# Test_Board.net
KiCad netlist of a schematic drawn in EAGLE
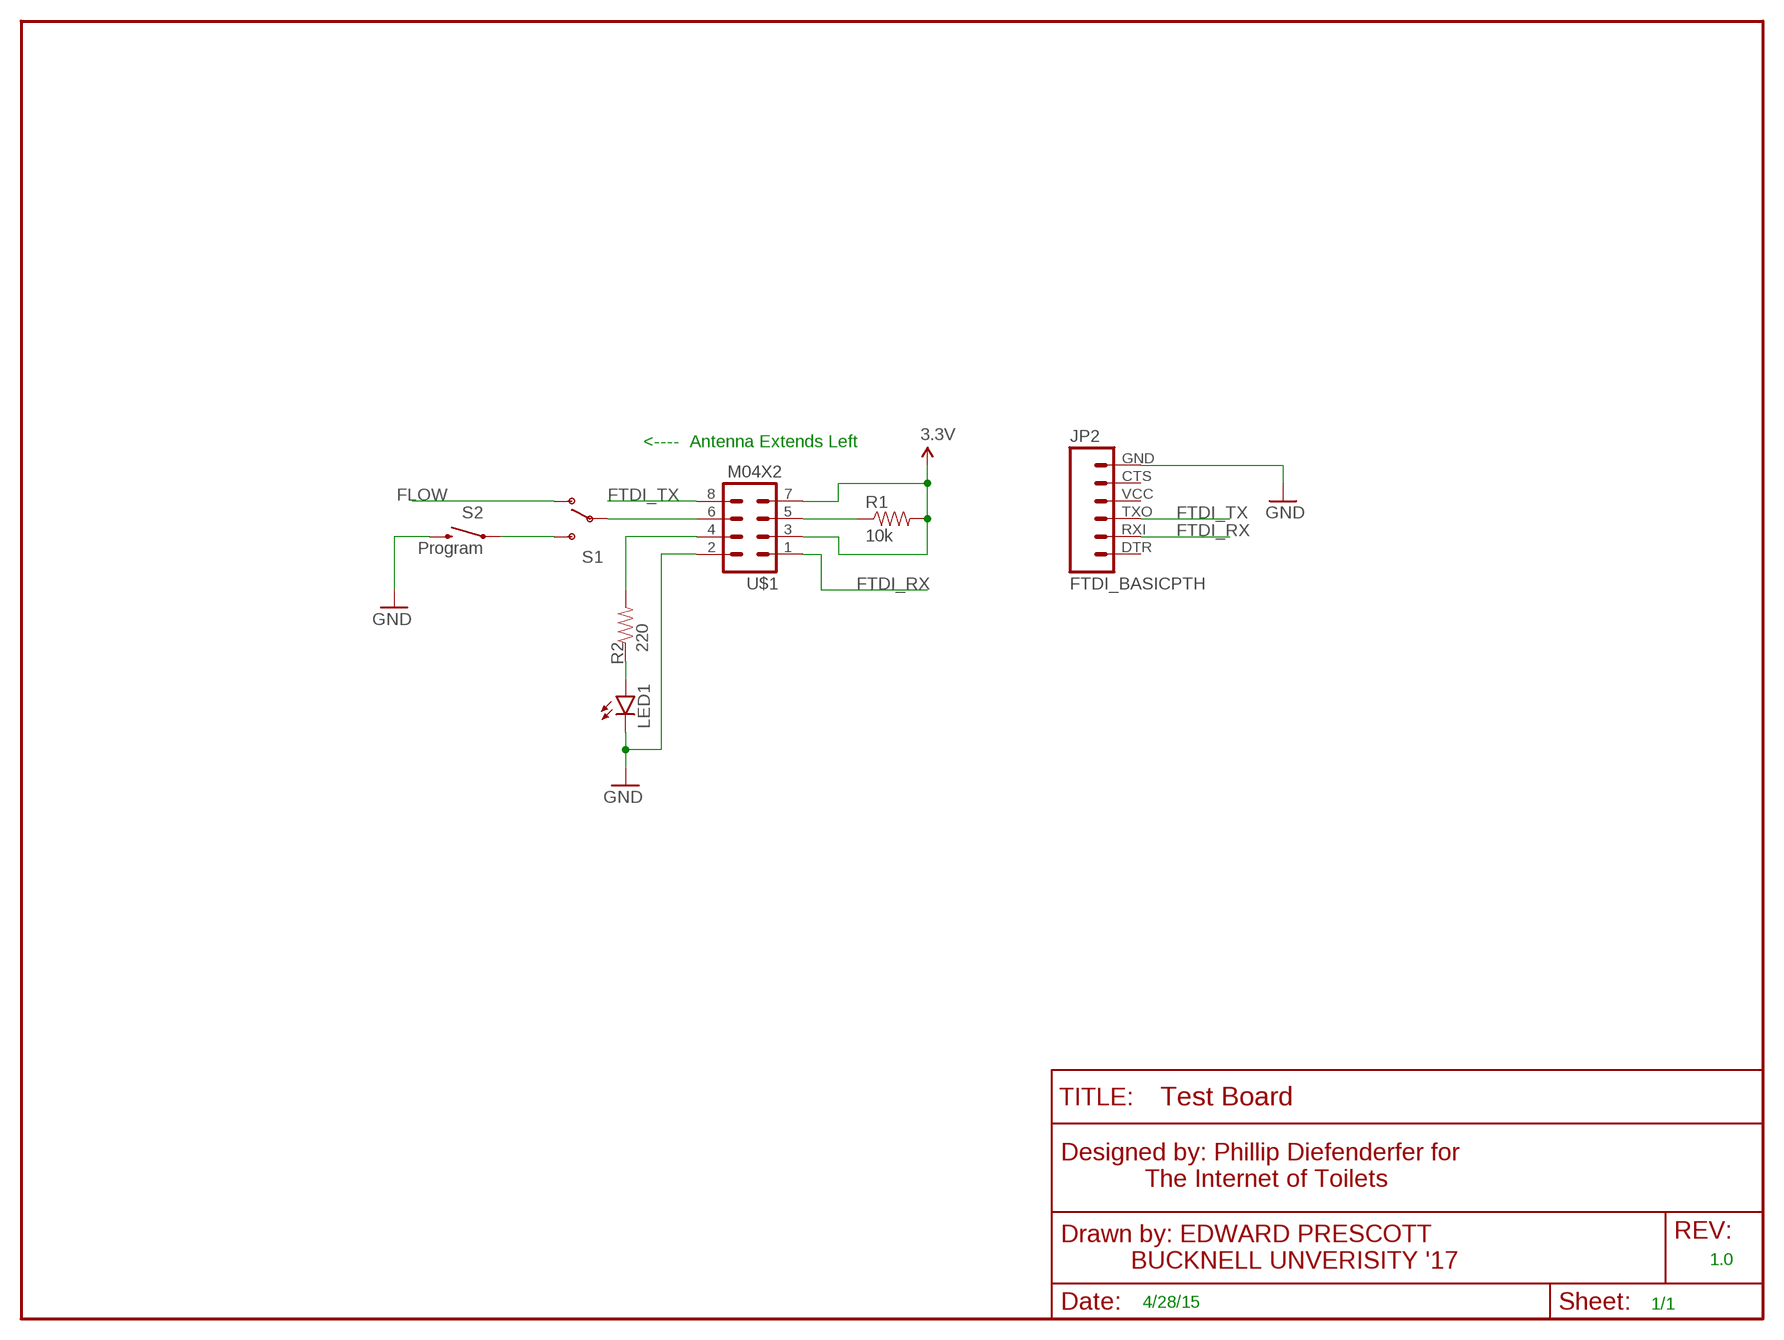
[diagram p0: schematic, sheet 1]

(export (version "E")
  (design (tool "Eeschema 10.0.6"))
  (components
    (comp (ref "FRAME1")
      (value "FRAME-LETTER")
      (footprint "eagle-import:CREATIVE_COMMONS")
      (libsource (lib "eagle-import") (part "FRAME-LETTER"))
    )
    (comp (ref "JP2")
      (value "FTDI_BASICPTH")
      (footprint "eagle-import:FTDI_BASIC")
      (libsource (lib "eagle-import") (part "FTDI_BASICPTH"))
    )
    (comp (ref "LED1")
      (value "LED-3MM-NO_SILK")
      (footprint "eagle-import:LED3MM-NS")
      (libsource (lib "eagle-import") (part "LED-3MM-NO_SILK"))
    )
    (comp (ref "R1")
      (value "10k")
      (footprint "eagle-import:AXIAL-0.3")
      (libsource (lib "eagle-import") (part "RESISTORAXIAL-0.3"))
    )
    (comp (ref "R2")
      (value "220")
      (footprint "eagle-import:AXIAL-0.3")
      (libsource (lib "eagle-import") (part "RESISTORAXIAL-0.3"))
    )
    (comp (ref "S1")
      (value "SWITCH-SPDTPTH")
      (footprint "eagle-import:SWITCH-SPDT")
      (libsource (lib "eagle-import") (part "SWITCH-SPDTPTH"))
    )
    (comp (ref "S2")
      (value "Program")
      (footprint "eagle-import:TACTILE-PTH")
      (libsource (lib "eagle-import") (part "SWITCH-MOMENTARY-2PTH"))
    )
    (comp (ref "U$1")
      (value "M04X2")
      (footprint "eagle-import:2X4")
      (libsource (lib "eagle-import") (part "M04X2"))
    )
  )
  (nets
    (net (code "1") (name "/FLOW") (class "Default")
      (node (ref "S1") (pin "1") (pinfunction "O_1") (pintype "passive"))
    )
    (net (code "2") (name "/FTDI_RX") (class "Default")
      (node (ref "JP2") (pin "RXI") (pinfunction "2_RXI") (pintype "passive"))
      (node (ref "U$1") (pin "1") (pinfunction "1_1") (pintype "passive"))
    )
    (net (code "3") (name "/FTDI_TX") (class "Default")
      (node (ref "JP2") (pin "TXO") (pinfunction "3_TXO") (pintype "passive"))
      (node (ref "U$1") (pin "8") (pinfunction "8_8") (pintype "passive"))
    )
    (net (code "4") (name "3.3V") (class "Default")
      (node (ref "R1") (pin "P$2") (pinfunction "2_P$2") (pintype "passive"))
      (node (ref "U$1") (pin "3") (pinfunction "3_3") (pintype "passive"))
      (node (ref "U$1") (pin "7") (pinfunction "7_7") (pintype "passive"))
    )
    (net (code "5") (name "GND") (class "Default")
      (node (ref "JP2") (pin "GND") (pinfunction "6_GND") (pintype "passive"))
      (node (ref "LED1") (pin "K") (pinfunction "C_K") (pintype "passive"))
      (node (ref "S2") (pin "3") (pinfunction "2_3") (pintype "passive"))
      (node (ref "U$1") (pin "2") (pinfunction "2_2") (pintype "passive"))
    )
    (net (code "6") (name "Net-(R1-1)") (class "Default")
      (node (ref "R1") (pin "P$1") (pinfunction "1_P$1") (pintype "passive"))
      (node (ref "U$1") (pin "5") (pinfunction "5_5") (pintype "passive"))
    )
    (net (code "7") (name "Net-(R2-1)") (class "Default")
      (node (ref "LED1") (pin "A") (pinfunction "A_A") (pintype "passive"))
      (node (ref "R2") (pin "P$1") (pinfunction "1_P$1") (pintype "passive"))
    )
    (net (code "8") (name "Net-(R2-2)") (class "Default")
      (node (ref "R2") (pin "P$2") (pinfunction "2_P$2") (pintype "passive"))
      (node (ref "U$1") (pin "4") (pinfunction "4_4") (pintype "passive"))
    )
    (net (code "9") (name "Net-(S1-P)") (class "Default")
      (node (ref "S1") (pin "2") (pinfunction "P_2") (pintype "passive"))
      (node (ref "U$1") (pin "6") (pinfunction "6_6") (pintype "passive"))
    )
    (net (code "10") (name "Net-(S1-S)") (class "Default")
      (node (ref "S1") (pin "3") (pinfunction "S_3") (pintype "passive"))
      (node (ref "S2") (pin "1") (pinfunction "1_1") (pintype "passive"))
    )
    (net (code "11") (name "unconnected-(JP2-1-PadDTR)") (class "Default")
      (node (ref "JP2") (pin "DTR") (pinfunction "1_DTR") (pintype "passive"))
    )
    (net (code "12") (name "unconnected-(JP2-4-PadVCC)") (class "Default")
      (node (ref "JP2") (pin "VCC") (pinfunction "4_VCC") (pintype "passive"))
    )
    (net (code "13") (name "unconnected-(JP2-5-PadCTS)") (class "Default")
      (node (ref "JP2") (pin "CTS") (pinfunction "5_CTS") (pintype "passive"))
    )
  )
)
